# ESP8266.net
KiCad netlist of a schematic drawn in Altium Designer
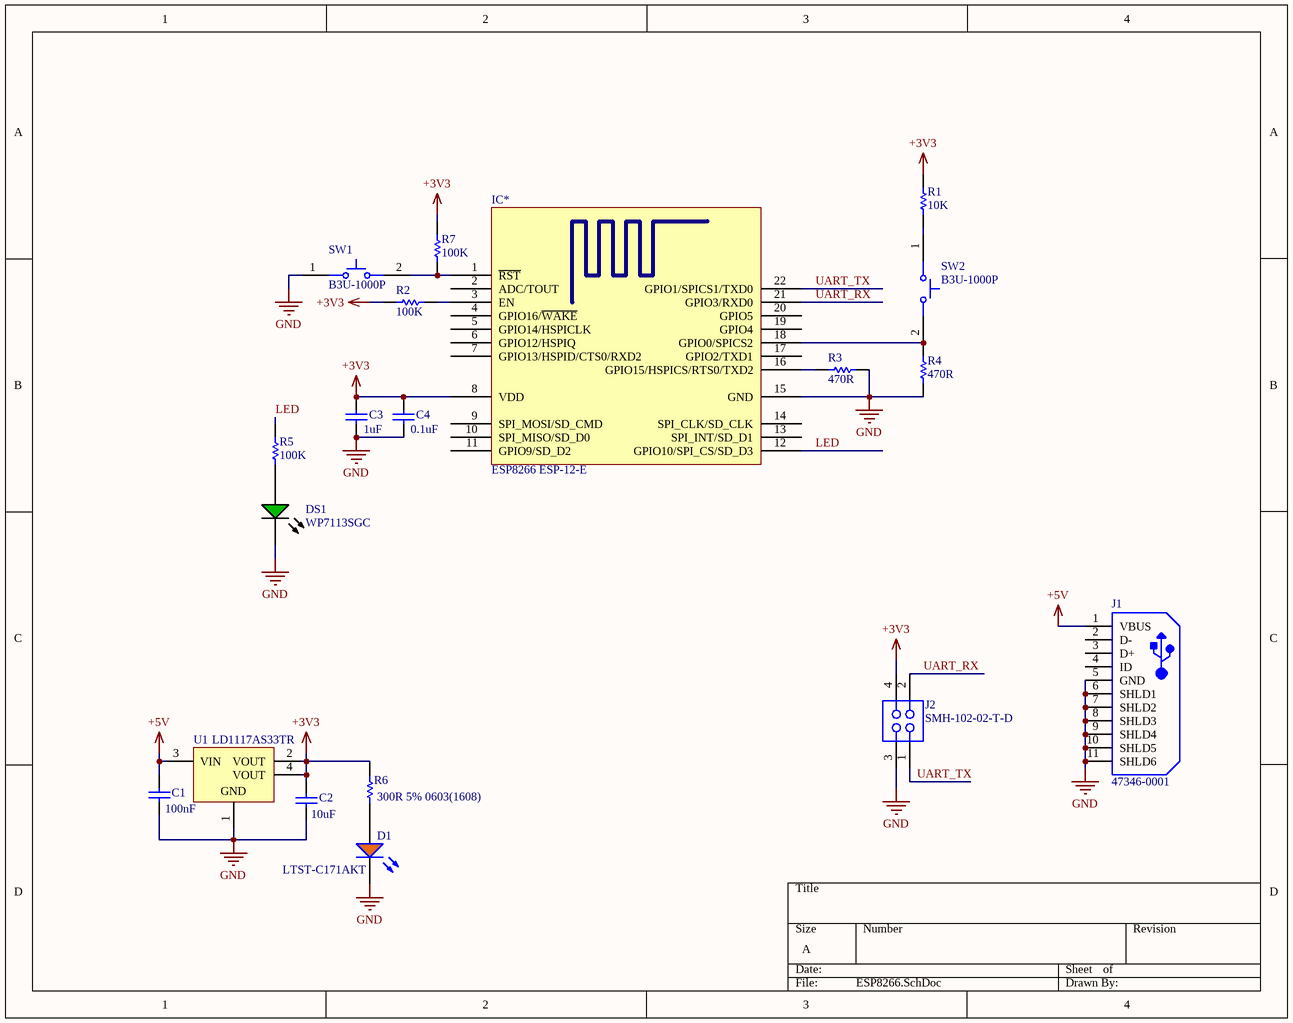
[diagram p0: ESP8266.SchDoc]

(export (version "E")
  (design (tool "Eeschema 10.0.6"))
  (components
    (comp (ref "C1")
      (value "100nF")
      (footprint "CAPC0805(2012)145_L")
      (description "0805 (2012 Metric) Chip Capacitor")
      (libsource (lib "Altium Content Vault") (part "CAP_5"))
    )
    (comp (ref "C2")
      (value "10uF")
      (footprint "CAPC0805(2012)145_L")
      (description "0805 (2012 Metric) Chip Capacitor")
      (libsource (lib "Altium Content Vault") (part "CAP_5"))
    )
    (comp (ref "C3")
      (value "1uF")
      (footprint "CAPC0805(2012)145_L")
      (description "0805 (2012 Metric) Chip Capacitor")
      (libsource (lib "Altium Content Vault") (part "CAP_5"))
    )
    (comp (ref "C4")
      (value "0.1uF")
      (footprint "CAPC0805(2012)145_L")
      (description "0805 (2012 Metric) Chip Capacitor")
      (libsource (lib "Altium Content Vault") (part "CAP_5"))
    )
    (comp (ref "D1")
      (value "LTST-C171AKT")
      (footprint "LTST-C171AKT_V")
      (description "LED AMBER CLR THIN 0805 SMD")
      (fields (field (name "MANUFACTURER") "Lite-On"))
      (libsource (lib "Altium Content Vault") (part "LED_AMBER_AC"))
    )
    (comp (ref "DS1")
      (value "WP7113SGC")
      (footprint "KING-WP7113SGC_V")
      (description "The Super Bright Green Source Color Device, 2.2 V, -40 to 85 degC, 2-Pin THD, RoHS, Tape and Reel")
      (libsource (lib "Altium Content Vault") (part "LED-GREEN-AK-2"))
    )
    (comp (ref "IC*")
      (value "ESP8266 ESP-12-E")
      (footprint "ESP8266:ESP8266 ESP-12-E")
      (libsource (lib "ESP8266") (part "ESP8266 ESP-12-E"))
    )
    (comp (ref "J1")
      (value "47346-0001")
      (footprint "MOLX-47346-0001-5_V")
      (description "Micro-USB B Receptacle with Flange, -30 to 85 degC, 5-Pin SMD, RoHS, Tape and Reel")
      (fields (field (name "MANUFACTURER") "Molex"))
      (libsource (lib "Altium Content Vault") (part "MOLX-47346-0001-5"))
    )
    (comp (ref "J2")
      (value "SMH-102-02-T-D")
      (footprint "SMTC-SMH-102-02-X-D")
      (description "SMT Horizontal Socket, -55 to 105 degC, 2.54 mm Pitch, 4-Pin, Female, RoHS")
      (fields (field (name "MANUFACTURER") "Samtec"))
      (libsource (lib "Altium Content Vault") (part "SMTC-SMH-102-02-X-D"))
    )
    (comp (ref "R1")
      (value "10K")
      (footprint "RESC0603(1608)_L")
      (description "0603 (1608 Metric) Chip Resistor")
      (libsource (lib "Altium Content Vault") (part "RES_3"))
    )
    (comp (ref "R2")
      (value "100K")
      (footprint "RESC0603(1608)_L")
      (description "0603 (1608 Metric) Chip Resistor")
      (libsource (lib "Altium Content Vault") (part "RES_3"))
    )
    (comp (ref "R3")
      (value "470R")
      (footprint "RESC0603(1608)_L")
      (description "0603 (1608 Metric) Chip Resistor")
      (libsource (lib "Altium Content Vault") (part "RES_3"))
    )
    (comp (ref "R4")
      (value "470R")
      (footprint "RESC0603(1608)_L")
      (description "0603 (1608 Metric) Chip Resistor")
      (libsource (lib "Altium Content Vault") (part "RES_3"))
    )
    (comp (ref "R5")
      (value "100K")
      (footprint "RESC0603(1608)_L")
      (description "0603 (1608 Metric) Chip Resistor")
      (libsource (lib "Altium Content Vault") (part "RES_3"))
    )
    (comp (ref "R6")
      (value "300R 5% 0603(1608)")
      (footprint "RESC0603(1608)_N")
      (description "100K 0.1W 5% 0603 (1608 Metric)  SMD")
      (fields (field (name "TOLERANCE") "5 %") (field (name "POWER") "0.1 W"))
      (libsource (lib "Altium Content Vault") (part "RES"))
    )
    (comp (ref "R7")
      (value "100K")
      (footprint "RESC0603(1608)_L")
      (description "0603 (1608 Metric) Chip Resistor")
      (libsource (lib "Altium Content Vault") (part "RES_3"))
    )
    (comp (ref "SW1")
      (value "B3U-1000P")
      (footprint "OMRON-B3U-1000_V")
      (description "Ultra-Small Tactile Switch, 0.05 A, 12 V, -25 to 70 degC, 2-Pin SMD, RoHS, Tape and Reel")
      (fields (field (name "MANUFACTURER") "Omron Electronic Components"))
      (libsource (lib "Altium Content Vault") (part "SW-SPST-NO-2"))
    )
    (comp (ref "SW2")
      (value "B3U-1000P")
      (footprint "OMRON-B3U-1000_V")
      (description "Ultra-Small Tactile Switch, 0.05 A, 12 V, -25 to 70 degC, 2-Pin SMD, RoHS, Tape and Reel")
      (fields (field (name "MANUFACTURER") "Omron Electronic Components"))
      (libsource (lib "Altium Content Vault") (part "SW-SPST-NO-2"))
    )
    (comp (ref "U1")
      (value "LD1117AS33TR")
      (footprint "SOT-223_M")
      (description "1A, Low Drop Positive Voltage Regulator, 3.3V, 4-Pin SOT-223, Tape and Reel")
      (libsource (lib "Altium Content Vault") (part "PM-REG-LD1117-SOT4"))
    )
  )
  (nets
    (net (code "1") (name "+3V3") (class "Default")
      (node (ref "C2") (pin "2") (pinfunction "2_2") (pintype "passive"))
      (node (ref "C3") (pin "2") (pinfunction "2_2") (pintype "passive"))
      (node (ref "C4") (pin "2") (pinfunction "2_2") (pintype "passive"))
      (node (ref "IC*") (pin "8") (pinfunction "VDD_8") (pintype "passive"))
      (node (ref "J2") (pin "4") (pinfunction "4_4") (pintype "passive"))
      (node (ref "R1") (pin "1") (pinfunction "1_1") (pintype "passive"))
      (node (ref "R2") (pin "1") (pinfunction "1_1") (pintype "passive"))
      (node (ref "R6") (pin "2") (pinfunction "2_2") (pintype "passive"))
      (node (ref "R7") (pin "2") (pinfunction "2_2") (pintype "passive"))
      (node (ref "U1") (pin "2") (pinfunction "VOUT_2") (pintype "power_in"))
      (node (ref "U1") (pin "4") (pinfunction "VOUT_4") (pintype "power_in"))
    )
    (net (code "2") (name "+5V") (class "Default")
      (node (ref "C1") (pin "2") (pinfunction "2_2") (pintype "passive"))
      (node (ref "J1") (pin "1") (pinfunction "VBUS_1") (pintype "passive"))
      (node (ref "U1") (pin "3") (pinfunction "VIN_3") (pintype "power_in"))
    )
    (net (code "3") (name "/LED") (class "Default")
      (node (ref "IC*") (pin "12") (pinfunction "GPIO10/SPI_CS/SD_D3_12") (pintype "passive"))
      (node (ref "R5") (pin "2") (pinfunction "2_2") (pintype "passive"))
    )
    (net (code "4") (name "/UART_RX") (class "Default")
      (node (ref "IC*") (pin "21") (pinfunction "GPIO3/RXD0_21") (pintype "passive"))
      (node (ref "J2") (pin "2") (pinfunction "2_2") (pintype "passive"))
    )
    (net (code "5") (name "/UART_TX") (class "Default")
      (node (ref "IC*") (pin "22") (pinfunction "GPIO1/SPICS1/TXD0_22") (pintype "passive"))
      (node (ref "J2") (pin "1") (pinfunction "1_1") (pintype "passive"))
    )
    (net (code "6") (name "GND") (class "Default")
      (node (ref "C1") (pin "1") (pinfunction "1_1") (pintype "passive"))
      (node (ref "C2") (pin "1") (pinfunction "1_1") (pintype "passive"))
      (node (ref "C3") (pin "1") (pinfunction "1_1") (pintype "passive"))
      (node (ref "C4") (pin "1") (pinfunction "1_1") (pintype "passive"))
      (node (ref "D1") (pin "C") (pinfunction "C_C") (pintype "passive"))
      (node (ref "DS1") (pin "2") (pinfunction "K_2") (pintype "passive"))
      (node (ref "IC*") (pin "15") (pinfunction "GND_15") (pintype "passive"))
      (node (ref "J1") (pin "10") (pinfunction "SHLD5_10") (pintype "passive"))
      (node (ref "J1") (pin "11") (pinfunction "SHLD6_11") (pintype "passive"))
      (node (ref "J1") (pin "5") (pinfunction "GND_5") (pintype "passive"))
      (node (ref "J1") (pin "6") (pinfunction "SHLD1_6") (pintype "passive"))
      (node (ref "J1") (pin "7") (pinfunction "SHLD2_7") (pintype "passive"))
      (node (ref "J1") (pin "8") (pinfunction "SHLD3_8") (pintype "passive"))
      (node (ref "J1") (pin "9") (pinfunction "SHLD4_9") (pintype "passive"))
      (node (ref "J2") (pin "3") (pinfunction "3_3") (pintype "passive"))
      (node (ref "R3") (pin "1") (pinfunction "1_1") (pintype "passive"))
      (node (ref "R4") (pin "1") (pinfunction "1_1") (pintype "passive"))
      (node (ref "SW1") (pin "1") (pinfunction "1_1") (pintype "passive"))
      (node (ref "U1") (pin "1") (pinfunction "GND_1") (pintype "power_in"))
    )
    (net (code "7") (name "Net-(D1-PadA)") (class "Default")
      (node (ref "D1") (pin "A") (pinfunction "A_A") (pintype "passive"))
      (node (ref "R6") (pin "1") (pinfunction "1_1") (pintype "passive"))
    )
    (net (code "8") (name "Net-(DS1-A)") (class "Default")
      (node (ref "DS1") (pin "1") (pinfunction "A_1") (pintype "passive"))
      (node (ref "R5") (pin "1") (pinfunction "1_1") (pintype "passive"))
    )
    (net (code "9") (name "Net-(IC*-EN)") (class "Default")
      (node (ref "IC*") (pin "3") (pinfunction "EN_3") (pintype "passive"))
      (node (ref "R2") (pin "2") (pinfunction "2_2") (pintype "passive"))
    )
    (net (code "10") (name "Net-(IC*-GPIO0{slash}SPICS2)") (class "Default")
      (node (ref "IC*") (pin "18") (pinfunction "GPIO0/SPICS2_18") (pintype "passive"))
      (node (ref "R4") (pin "2") (pinfunction "2_2") (pintype "passive"))
      (node (ref "SW2") (pin "2") (pinfunction "2_2") (pintype "passive"))
    )
    (net (code "11") (name "Net-(IC*-GPIO15{slash}HSPICS{slash}RTS0{slash}TXD2)") (class "Default")
      (node (ref "IC*") (pin "16") (pinfunction "GPIO15/HSPICS/RTS0/TXD2_16") (pintype "passive"))
      (node (ref "R3") (pin "2") (pinfunction "2_2") (pintype "passive"))
    )
    (net (code "12") (name "Net-(IC*-~{RST})") (class "Default")
      (node (ref "IC*") (pin "1") (pinfunction "~{RST}_1") (pintype "passive"))
      (node (ref "R7") (pin "1") (pinfunction "1_1") (pintype "passive"))
      (node (ref "SW1") (pin "2") (pinfunction "2_2") (pintype "passive"))
    )
    (net (code "13") (name "Net-(R1-Pad2)") (class "Default")
      (node (ref "R1") (pin "2") (pinfunction "2_2") (pintype "passive"))
      (node (ref "SW2") (pin "1") (pinfunction "1_1") (pintype "passive"))
    )
    (net (code "14") (name "unconnected-(IC*-ADC{slash}TOUT-Pad2)") (class "Default")
      (node (ref "IC*") (pin "2") (pinfunction "ADC/TOUT_2") (pintype "passive"))
    )
    (net (code "15") (name "unconnected-(IC*-GPIO2{slash}TXD1-Pad17)") (class "Default")
      (node (ref "IC*") (pin "17") (pinfunction "GPIO2/TXD1_17") (pintype "passive"))
    )
    (net (code "16") (name "unconnected-(IC*-GPIO4-Pad19)") (class "Default")
      (node (ref "IC*") (pin "19") (pinfunction "GPIO4_19") (pintype "passive"))
    )
    (net (code "17") (name "unconnected-(IC*-GPIO5-Pad20)") (class "Default")
      (node (ref "IC*") (pin "20") (pinfunction "GPIO5_20") (pintype "passive"))
    )
    (net (code "18") (name "unconnected-(IC*-GPIO9{slash}SD_D2-Pad11)") (class "Default")
      (node (ref "IC*") (pin "11") (pinfunction "GPIO9/SD_D2_11") (pintype "passive"))
    )
    (net (code "19") (name "unconnected-(IC*-GPIO12{slash}HSPIQ-Pad6)") (class "Default")
      (node (ref "IC*") (pin "6") (pinfunction "GPIO12/HSPIQ_6") (pintype "passive"))
    )
    (net (code "20") (name "unconnected-(IC*-GPIO13{slash}HSPID{slash}CTS0{slash}RXD2-Pad7)") (class "Default")
      (node (ref "IC*") (pin "7") (pinfunction "GPIO13/HSPID/CTS0/RXD2_7") (pintype "passive"))
    )
    (net (code "21") (name "unconnected-(IC*-GPIO14{slash}HSPICLK-Pad5)") (class "Default")
      (node (ref "IC*") (pin "5") (pinfunction "GPIO14/HSPICLK_5") (pintype "passive"))
    )
    (net (code "22") (name "unconnected-(IC*-GPIO16{slash}~{WAKE}-Pad4)") (class "Default")
      (node (ref "IC*") (pin "4") (pinfunction "GPIO16/~{WAKE}_4") (pintype "passive"))
    )
    (net (code "23") (name "unconnected-(IC*-SPI_CLK{slash}SD_CLK-Pad14)") (class "Default")
      (node (ref "IC*") (pin "14") (pinfunction "SPI_CLK/SD_CLK_14") (pintype "passive"))
    )
    (net (code "24") (name "unconnected-(IC*-SPI_INT{slash}SD_D1-Pad13)") (class "Default")
      (node (ref "IC*") (pin "13") (pinfunction "SPI_INT/SD_D1_13") (pintype "passive"))
    )
    (net (code "25") (name "unconnected-(IC*-SPI_MISO{slash}SD_D0-Pad10)") (class "Default")
      (node (ref "IC*") (pin "10") (pinfunction "SPI_MISO/SD_D0_10") (pintype "passive"))
    )
    (net (code "26") (name "unconnected-(IC*-SPI_MOSI{slash}SD_CMD-Pad9)") (class "Default")
      (node (ref "IC*") (pin "9") (pinfunction "SPI_MOSI/SD_CMD_9") (pintype "passive"))
    )
    (net (code "27") (name "unconnected-(J1-D+-Pad3)") (class "Default")
      (node (ref "J1") (pin "3") (pinfunction "D+_3") (pintype "passive"))
    )
    (net (code "28") (name "unconnected-(J1-D--Pad2)") (class "Default")
      (node (ref "J1") (pin "2") (pinfunction "D-_2") (pintype "passive"))
    )
    (net (code "29") (name "unconnected-(J1-ID-Pad4)") (class "Default")
      (node (ref "J1") (pin "4") (pinfunction "ID_4") (pintype "passive"))
    )
  )
)
